# Sheet1.net
KiCad netlist of a schematic drawn in Altium Designer
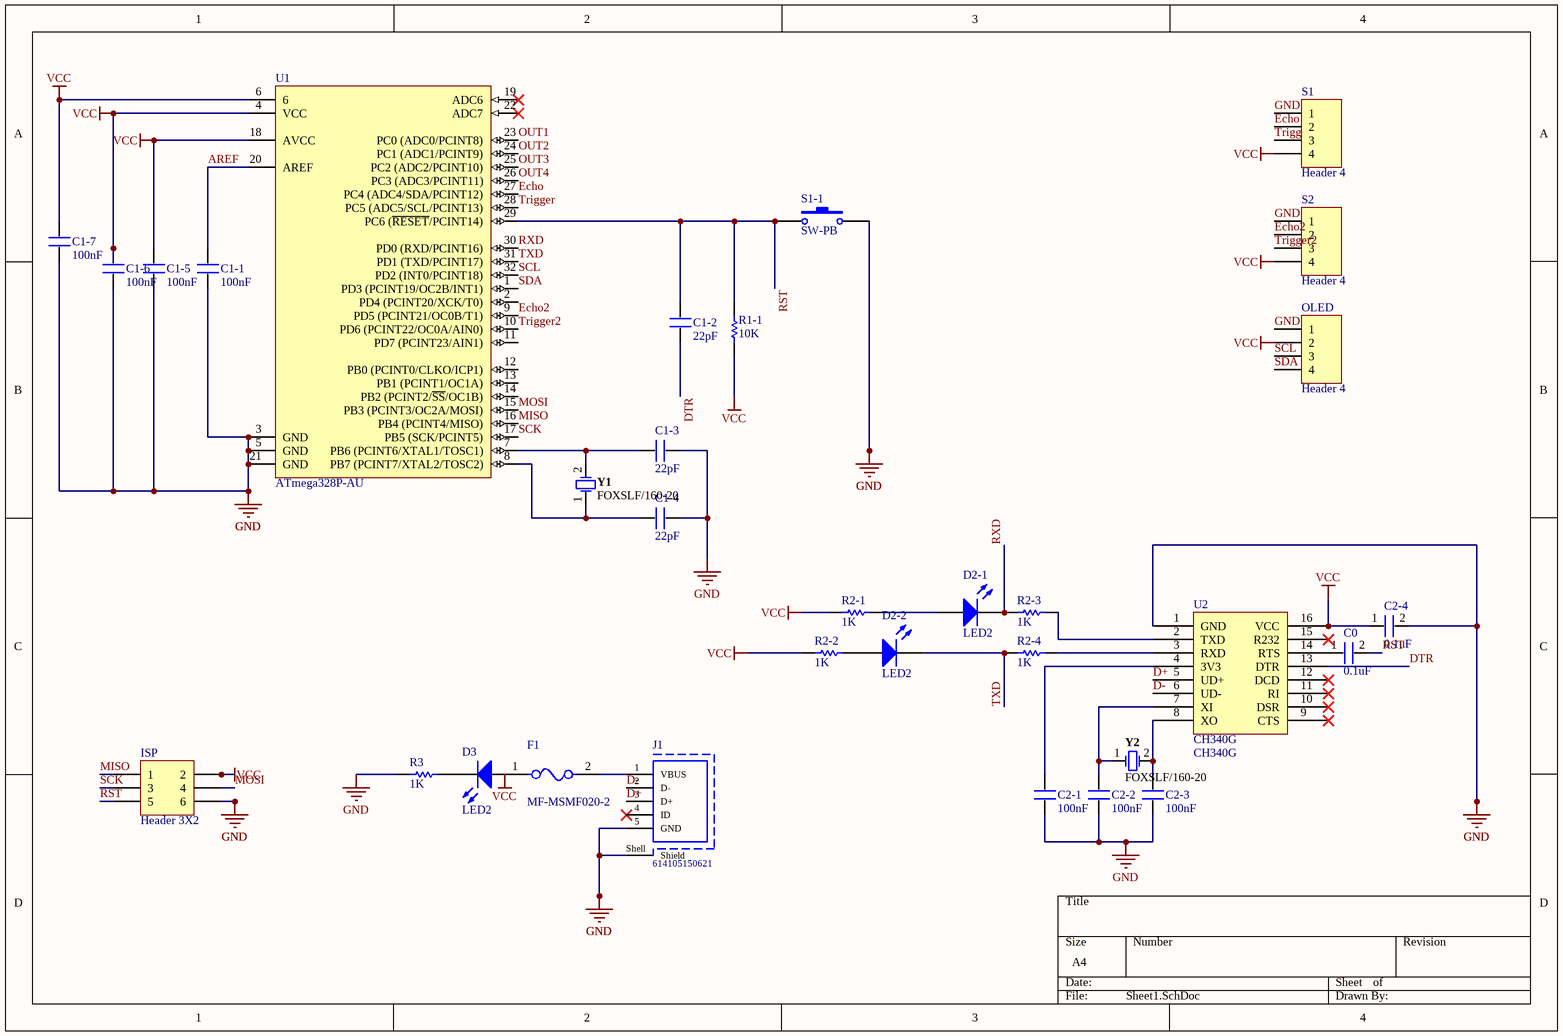
[diagram p0: Sheet1.SchDoc]

(export (version "E")
  (design (tool "Eeschema 10.0.6"))
  (components
    (comp (ref "C0")
      (value "0.1uF")
      (footprint "0805")
      (description "Capacitor")
      (fields (field (name "Comment") "CAP"))
      (libsource (lib "") (part "CAP_1"))
    )
    (comp (ref "C1-1")
      (value "100nF")
      (footprint "0805")
      (description "Capacitor")
      (fields (field (name "Comment") "CAP"))
      (libsource (lib "lib") (part "CAP"))
    )
    (comp (ref "C1-2")
      (value "22pF")
      (footprint "0805")
      (description "Capacitor")
      (fields (field (name "Comment") "CAP"))
      (libsource (lib "lib") (part "CAP"))
    )
    (comp (ref "C1-3")
      (value "22pF")
      (footprint "0805")
      (description "Capacitor")
      (fields (field (name "Comment") "CAP"))
      (libsource (lib "lib") (part "CAP"))
    )
    (comp (ref "C1-4")
      (value "22pF")
      (footprint "0805")
      (description "Capacitor")
      (fields (field (name "Comment") "CAP"))
      (libsource (lib "lib") (part "CAP"))
    )
    (comp (ref "C1-5")
      (value "100nF")
      (footprint "0805")
      (description "Capacitor")
      (fields (field (name "Comment") "CAP"))
      (libsource (lib "lib") (part "CAP"))
    )
    (comp (ref "C1-6")
      (value "100nF")
      (footprint "0805")
      (description "Capacitor")
      (fields (field (name "Comment") "CAP"))
      (libsource (lib "lib") (part "CAP"))
    )
    (comp (ref "C1-7")
      (value "100nF")
      (footprint "0805")
      (description "Capacitor")
      (fields (field (name "Comment") "CAP"))
      (libsource (lib "lib") (part "CAP"))
    )
    (comp (ref "C2-1")
      (value "100nF")
      (footprint "0805")
      (description "Capacitor")
      (fields (field (name "Comment") "CAP"))
      (libsource (lib "lib") (part "CAP"))
    )
    (comp (ref "C2-2")
      (value "100nF")
      (footprint "0805")
      (description "Capacitor")
      (fields (field (name "Comment") "CAP"))
      (libsource (lib "lib") (part "CAP"))
    )
    (comp (ref "C2-3")
      (value "100nF")
      (footprint "0805")
      (description "Capacitor")
      (fields (field (name "Comment") "CAP"))
      (libsource (lib "lib") (part "CAP"))
    )
    (comp (ref "C2-4")
      (value "0.1uF")
      (footprint "0805")
      (description "Capacitor")
      (fields (field (name "Comment") "CAP"))
      (libsource (lib "") (part "CAP_1"))
    )
    (comp (ref "D2-1")
      (value "LED2")
      (footprint "3.2X1.6X1.1")
      (description "Typical RED, GREEN, YELLOW, AMBER GaAs LED")
      (fields (field (name "PUBLISHER") "Altium Limited"))
      (libsource (lib "lib") (part "LED2"))
    )
    (comp (ref "D2-2")
      (value "LED2")
      (footprint "3.2X1.6X1.1")
      (description "Typical RED, GREEN, YELLOW, AMBER GaAs LED")
      (fields (field (name "PUBLISHER") "Altium Limited"))
      (libsource (lib "lib") (part "LED2"))
    )
    (comp (ref "D3")
      (value "LED2")
      (footprint "3.2X1.6X1.1")
      (description "Typical RED, GREEN, YELLOW, AMBER GaAs LED")
      (fields (field (name "PUBLISHER") "Altium Limited"))
      (libsource (lib "lib") (part "LED2"))
    )
    (comp (ref "F1")
      (value "MF-MSMF020-2")
      (footprint "FP-MF-MSMF020-2-MFG")
      (description "PTC RESET FUSE 30V 200MA 1812")
      (fields
        (field (name "MANUFACTURER") "Bourns")
        (field (name "OCTOPART") "https://octopart.com/mf-msmf020-2-bourns-19289")
      )
      (libsource (lib "lib") (part "CMP-07400-000027-1"))
    )
    (comp (ref "ISP")
      (value "Header 3X2")
      (footprint "HDR2X3")
      (description "Header, 3-Pin, Dual row")
      (fields (field (name "PUBLISHER") "Altium Limited"))
      (libsource (lib "Miscellaneous Connectors") (part "Header 3X2"))
    )
    (comp (ref "J1")
      (value "614105150621")
      (footprint "629105150921")
      (description "Micro USB 2.0 Type AB Receptacle WR-COM, Vertical, THT")
      (fields (field (name "MANUFACTURER") "Wurth Elektronik") (field (name "PUBLISHER") "WurthElektronik"))
      (libsource (lib "lib") (part "CMP-1502-03251-1"))
    )
    (comp (ref "OLED")
      (value "Header 4")
      (footprint "HDR1X4")
      (description "Header, 4-Pin")
      (fields (field (name "PUBLISHER") "Altium Limited"))
      (libsource (lib "Miscellaneous Connectors") (part "Header 4"))
    )
    (comp (ref "R1-1")
      (value "RES")
      (footprint "0805")
      (description "Resistor")
      (fields (field (name "VAULE") "10K"))
      (libsource (lib "lib") (part "RES"))
    )
    (comp (ref "R2-1")
      (value "RES")
      (footprint "0805")
      (description "Resistor")
      (fields (field (name "VAULE") "1K"))
      (libsource (lib "lib") (part "RES"))
    )
    (comp (ref "R2-2")
      (value "RES")
      (footprint "0805")
      (description "Resistor")
      (fields (field (name "VAULE") "1K"))
      (libsource (lib "lib") (part "RES"))
    )
    (comp (ref "R2-3")
      (value "RES")
      (footprint "0805")
      (description "Resistor")
      (fields (field (name "VAULE") "1K"))
      (libsource (lib "lib") (part "RES"))
    )
    (comp (ref "R2-4")
      (value "RES")
      (footprint "0805")
      (description "Resistor")
      (fields (field (name "VAULE") "1K"))
      (libsource (lib "lib") (part "RES"))
    )
    (comp (ref "R3")
      (value "RES")
      (footprint "0805")
      (description "Resistor")
      (fields (field (name "VAULE") "1K"))
      (libsource (lib "lib") (part "RES"))
    )
    (comp (ref "S1")
      (value "Header 4")
      (footprint "HDR1X4")
      (description "Header, 4-Pin")
      (fields (field (name "PUBLISHER") "Altium Limited"))
      (libsource (lib "Miscellaneous Connectors") (part "Header 4"))
    )
    (comp (ref "S1-1")
      (value "SW-PB")
      (footprint "SPST-2")
      (description "Switch")
      (fields (field (name "PUBLISHER") "Altium Limited"))
      (libsource (lib "lib") (part "SW-PB"))
    )
    (comp (ref "S2")
      (value "Header 4")
      (footprint "HDR1X4")
      (description "Header, 4-Pin")
      (fields (field (name "PUBLISHER") "Altium Limited"))
      (libsource (lib "Miscellaneous Connectors") (part "Header 4"))
    )
    (comp (ref "U1")
      (value "ATmega328P-AU")
      (footprint "32A_L - duplicate")
      (libsource (lib "lib") (part "CMP-0095-00269-2"))
    )
    (comp (ref "U2")
      (value "CH340G")
      (footprint "SOIC127P600X170-16N")
      (libsource (lib "lib") (part "CH340G"))
    )
    (comp (ref "Y1")
      (value "FOXSLF/160-20")
      (footprint "FOX-FOXSLF160-20")
      (description "Resistance Weld Thru-Hole Crystal, 16 MHz, -20 to 70 degC, 2-Pin THD, RoHS, Bulk")
      (fields (field (name "TOLERANCE") "1%"))
      (libsource (lib "lib") (part "CMP-1749-00003-1"))
    )
    (comp (ref "Y2")
      (value "FOXSLF/160-20")
      (footprint "FOX-FOXSLF160-20")
      (description "Resistance Weld Thru-Hole Crystal, 16 MHz, -20 to 70 degC, 2-Pin THD, RoHS, Bulk")
      (fields (field (name "TOLERANCE") "1%"))
      (libsource (lib "lib") (part "CMP-1749-00003-1"))
    )
  )
  (nets
    (net (code "1") (name "/AREF") (class "Default")
      (node (ref "C1-1") (pin "2") (pintype "passive"))
      (node (ref "U1") (pin "20") (pinfunction "AREF_20") (pintype "passive"))
    )
    (net (code "2") (name "/D+") (class "Default")
      (node (ref "J1") (pin "3") (pinfunction "D+_3") (pintype "passive"))
      (node (ref "U2") (pin "5") (pinfunction "UD+_5") (pintype "passive"))
    )
    (net (code "3") (name "/D-") (class "Default")
      (node (ref "J1") (pin "2") (pinfunction "D-_2") (pintype "passive"))
      (node (ref "U2") (pin "6") (pinfunction "UD-_6") (pintype "passive"))
    )
    (net (code "4") (name "/DTR") (class "Default")
      (node (ref "C1-2") (pin "1") (pintype "passive"))
      (node (ref "U2") (pin "13") (pinfunction "DTR_13") (pintype "passive"))
    )
    (net (code "5") (name "/Echo") (class "Default")
      (node (ref "S1") (pin "2") (pinfunction "2_2") (pintype "passive"))
      (node (ref "U1") (pin "27") (pinfunction "PC4_(ADC4/SDA/PCINT12)_27") (pintype "bidirectional"))
    )
    (net (code "6") (name "/Echo2") (class "Default")
      (node (ref "S2") (pin "2") (pinfunction "2_2") (pintype "passive"))
      (node (ref "U1") (pin "9") (pinfunction "PD5_(PCINT21/OC0B/T1)_9") (pintype "bidirectional"))
    )
    (net (code "7") (name "/MISO") (class "Default")
      (node (ref "ISP") (pin "1") (pinfunction "1_1") (pintype "passive"))
      (node (ref "U1") (pin "16") (pinfunction "PB4_(PCINT4/MISO)_16") (pintype "bidirectional"))
    )
    (net (code "8") (name "/MOSI") (class "Default")
      (node (ref "ISP") (pin "4") (pinfunction "4_4") (pintype "passive"))
      (node (ref "U1") (pin "15") (pinfunction "PB3_(PCINT3/OC2A/MOSI)_15") (pintype "bidirectional"))
    )
    (net (code "9") (name "/OUT1") (class "Default")
      (node (ref "U1") (pin "23") (pinfunction "PC0_(ADC0/PCINT8)_23") (pintype "bidirectional"))
    )
    (net (code "10") (name "/OUT2") (class "Default")
      (node (ref "U1") (pin "24") (pinfunction "PC1_(ADC1/PCINT9)_24") (pintype "bidirectional"))
    )
    (net (code "11") (name "/OUT3") (class "Default")
      (node (ref "U1") (pin "25") (pinfunction "PC2_(ADC2/PCINT10)_25") (pintype "bidirectional"))
    )
    (net (code "12") (name "/OUT4") (class "Default")
      (node (ref "U1") (pin "26") (pinfunction "PC3_(ADC3/PCINT11)_26") (pintype "bidirectional"))
    )
    (net (code "13") (name "/RST") (class "Default")
      (node (ref "C0") (pin "2") (pinfunction "2_2") (pintype "passive"))
      (node (ref "C1-2") (pin "2") (pintype "passive"))
      (node (ref "ISP") (pin "5") (pinfunction "5_5") (pintype "passive"))
      (node (ref "R1-1") (pin "1") (pinfunction "1_1") (pintype "passive"))
      (node (ref "S1-1") (pin "1") (pinfunction "1_1") (pintype "passive"))
      (node (ref "U1") (pin "29") (pinfunction "PC6_(~{RESET}/PCINT14)_29") (pintype "bidirectional"))
    )
    (net (code "14") (name "/RXD") (class "Default")
      (node (ref "D2-1") (pin "2") (pinfunction "K_2") (pintype "passive"))
      (node (ref "R2-3") (pin "1") (pinfunction "1_1") (pintype "passive"))
      (node (ref "U1") (pin "30") (pinfunction "PD0_(RXD/PCINT16)_30") (pintype "bidirectional"))
    )
    (net (code "15") (name "/SCK") (class "Default")
      (node (ref "ISP") (pin "3") (pinfunction "3_3") (pintype "passive"))
      (node (ref "U1") (pin "17") (pinfunction "PB5_(SCK/PCINT5)_17") (pintype "bidirectional"))
    )
    (net (code "16") (name "/SCL") (class "Default")
      (node (ref "OLED") (pin "3") (pinfunction "3_3") (pintype "passive"))
      (node (ref "U1") (pin "32") (pinfunction "PD2_(INT0/PCINT18)_32") (pintype "bidirectional"))
    )
    (net (code "17") (name "/SDA") (class "Default")
      (node (ref "OLED") (pin "4") (pinfunction "4_4") (pintype "passive"))
      (node (ref "U1") (pin "1") (pinfunction "PD3_(PCINT19/OC2B/INT1)_1") (pintype "bidirectional"))
    )
    (net (code "18") (name "/TXD") (class "Default")
      (node (ref "D2-2") (pin "2") (pinfunction "K_2") (pintype "passive"))
      (node (ref "R2-4") (pin "1") (pinfunction "1_1") (pintype "passive"))
      (node (ref "U1") (pin "31") (pinfunction "PD1_(TXD/PCINT17)_31") (pintype "bidirectional"))
    )
    (net (code "19") (name "/Trigger") (class "Default")
      (node (ref "S1") (pin "3") (pinfunction "3_3") (pintype "passive"))
      (node (ref "U1") (pin "28") (pinfunction "PC5_(ADC5/SCL/PCINT13)_28") (pintype "bidirectional"))
    )
    (net (code "20") (name "/Trigger2") (class "Default")
      (node (ref "S2") (pin "3") (pinfunction "3_3") (pintype "passive"))
      (node (ref "U1") (pin "10") (pinfunction "PD6_(PCINT22/OC0A/AIN0)_10") (pintype "bidirectional"))
    )
    (net (code "21") (name "GND") (class "Default")
      (node (ref "C1-1") (pin "1") (pintype "passive"))
      (node (ref "C1-3") (pin "2") (pintype "passive"))
      (node (ref "C1-4") (pin "2") (pintype "passive"))
      (node (ref "C1-5") (pin "1") (pintype "passive"))
      (node (ref "C1-6") (pin "1") (pintype "passive"))
      (node (ref "C1-7") (pin "1") (pintype "passive"))
      (node (ref "C2-1") (pin "1") (pintype "passive"))
      (node (ref "C2-2") (pin "1") (pintype "passive"))
      (node (ref "C2-3") (pin "1") (pintype "passive"))
      (node (ref "C2-4") (pin "2") (pinfunction "2_2") (pintype "passive"))
      (node (ref "ISP") (pin "6") (pinfunction "6_6") (pintype "passive"))
      (node (ref "J1") (pin "5") (pinfunction "GND_5") (pintype "passive"))
      (node (ref "J1") (pin "Shell") (pinfunction "Shield_Shell") (pintype "passive"))
      (node (ref "OLED") (pin "1") (pinfunction "1_1") (pintype "passive"))
      (node (ref "R3") (pin "1") (pinfunction "1_1") (pintype "passive"))
      (node (ref "S1") (pin "1") (pinfunction "1_1") (pintype "passive"))
      (node (ref "S1-1") (pin "2") (pinfunction "2_2") (pintype "passive"))
      (node (ref "S2") (pin "1") (pinfunction "1_1") (pintype "passive"))
      (node (ref "U1") (pin "21") (pinfunction "GND_21") (pintype "power_in"))
      (node (ref "U1") (pin "3") (pinfunction "GND_3") (pintype "power_in"))
      (node (ref "U1") (pin "5") (pinfunction "GND_5") (pintype "power_in"))
      (node (ref "U2") (pin "1") (pinfunction "GND_1") (pintype "passive"))
    )
    (net (code "22") (name "Net-(D2-1-A)") (class "Default")
      (node (ref "D2-1") (pin "1") (pinfunction "A_1") (pintype "passive"))
      (node (ref "R2-1") (pin "2") (pinfunction "2_2") (pintype "passive"))
    )
    (net (code "23") (name "Net-(D2-2-A)") (class "Default")
      (node (ref "D2-2") (pin "1") (pinfunction "A_1") (pintype "passive"))
      (node (ref "R2-2") (pin "2") (pinfunction "2_2") (pintype "passive"))
    )
    (net (code "24") (name "Net-(D3-K)") (class "Default")
      (node (ref "D3") (pin "2") (pinfunction "K_2") (pintype "passive"))
      (node (ref "R3") (pin "2") (pinfunction "2_2") (pintype "passive"))
    )
    (net (code "25") (name "Net-(J1-VBUS)") (class "Default")
      (node (ref "F1") (pin "2") (pinfunction "2_2") (pintype "passive"))
      (node (ref "J1") (pin "1") (pinfunction "VBUS_1") (pintype "passive"))
    )
    (net (code "26") (name "Net-(U1-PB6_(PCINT6{slash}XTAL1{slash}TOSC1))") (class "Default")
      (node (ref "C1-3") (pin "1") (pintype "passive"))
      (node (ref "U1") (pin "7") (pinfunction "PB6_(PCINT6/XTAL1/TOSC1)_7") (pintype "bidirectional"))
      (node (ref "Y1") (pin "2") (pinfunction "2_2") (pintype "passive"))
    )
    (net (code "27") (name "Net-(U1-PB7_(PCINT7{slash}XTAL2{slash}TOSC2))") (class "Default")
      (node (ref "C1-4") (pin "1") (pintype "passive"))
      (node (ref "U1") (pin "8") (pinfunction "PB7_(PCINT7/XTAL2/TOSC2)_8") (pintype "bidirectional"))
      (node (ref "Y1") (pin "1") (pinfunction "1_1") (pintype "passive"))
    )
    (net (code "28") (name "Net-(U2-3V3)") (class "Default")
      (node (ref "C2-1") (pin "2") (pintype "passive"))
      (node (ref "U2") (pin "4") (pinfunction "3V3_4") (pintype "passive"))
    )
    (net (code "29") (name "Net-(U2-RTS)") (class "Default")
      (node (ref "C0") (pin "1") (pinfunction "1_1") (pintype "passive"))
      (node (ref "U2") (pin "14") (pinfunction "RTS_14") (pintype "passive"))
    )
    (net (code "30") (name "Net-(U2-RXD)") (class "Default")
      (node (ref "R2-4") (pin "2") (pinfunction "2_2") (pintype "passive"))
      (node (ref "U2") (pin "3") (pinfunction "RXD_3") (pintype "passive"))
    )
    (net (code "31") (name "Net-(U2-TXD)") (class "Default")
      (node (ref "R2-3") (pin "2") (pinfunction "2_2") (pintype "passive"))
      (node (ref "U2") (pin "2") (pinfunction "TXD_2") (pintype "passive"))
    )
    (net (code "32") (name "Net-(U2-XI)") (class "Default")
      (node (ref "C2-2") (pin "2") (pintype "passive"))
      (node (ref "U2") (pin "7") (pinfunction "XI_7") (pintype "passive"))
      (node (ref "Y2") (pin "1") (pinfunction "1_1") (pintype "passive"))
    )
    (net (code "33") (name "Net-(U2-XO)") (class "Default")
      (node (ref "C2-3") (pin "2") (pintype "passive"))
      (node (ref "U2") (pin "8") (pinfunction "XO_8") (pintype "passive"))
      (node (ref "Y2") (pin "2") (pinfunction "2_2") (pintype "passive"))
    )
    (net (code "34") (name "VCC") (class "Default")
      (node (ref "C1-5") (pin "2") (pintype "passive"))
      (node (ref "C1-6") (pin "2") (pintype "passive"))
      (node (ref "C1-7") (pin "2") (pintype "passive"))
      (node (ref "C2-4") (pin "1") (pinfunction "1_1") (pintype "passive"))
      (node (ref "F1") (pin "1") (pinfunction "1_1") (pintype "passive"))
      (node (ref "ISP") (pin "2") (pinfunction "2_2") (pintype "passive"))
      (node (ref "OLED") (pin "2") (pinfunction "2_2") (pintype "passive"))
      (node (ref "R1-1") (pin "2") (pinfunction "2_2") (pintype "passive"))
      (node (ref "R2-1") (pin "1") (pinfunction "1_1") (pintype "passive"))
      (node (ref "R2-2") (pin "1") (pinfunction "1_1") (pintype "passive"))
      (node (ref "S1") (pin "4") (pinfunction "4_4") (pintype "passive"))
      (node (ref "S2") (pin "4") (pinfunction "4_4") (pintype "passive"))
      (node (ref "U1") (pin "18") (pinfunction "AVCC_18") (pintype "power_in"))
      (node (ref "U1") (pin "4") (pinfunction "VCC_4") (pintype "power_in"))
      (node (ref "U1") (pin "6") (pinfunction "6_6") (pintype "power_in"))
      (node (ref "U2") (pin "16") (pinfunction "VCC_16") (pintype "passive"))
    )
    (net (code "35") (name "unconnected-(D3-A-Pad1)") (class "Default")
      (node (ref "D3") (pin "1") (pinfunction "A_1") (pintype "passive"))
    )
    (net (code "36") (name "unconnected-(J1-ID-Pad4)") (class "Default")
      (node (ref "J1") (pin "4") (pinfunction "ID_4") (pintype "passive+no_connect"))
    )
    (net (code "37") (name "unconnected-(U1-ADC6-Pad19)") (class "Default")
      (node (ref "U1") (pin "19") (pinfunction "ADC6_19") (pintype "input+no_connect"))
    )
    (net (code "38") (name "unconnected-(U1-ADC7-Pad22)") (class "Default")
      (node (ref "U1") (pin "22") (pinfunction "ADC7_22") (pintype "input+no_connect"))
    )
    (net (code "39") (name "unconnected-(U1-PB0_(PCINT0{slash}CLKO{slash}ICP1)-Pad12)") (class "Default")
      (node (ref "U1") (pin "12") (pinfunction "PB0_(PCINT0/CLKO/ICP1)_12") (pintype "bidirectional"))
    )
    (net (code "40") (name "unconnected-(U1-PB1_(PCINT1{slash}OC1A)-Pad13)") (class "Default")
      (node (ref "U1") (pin "13") (pinfunction "PB1_(PCINT1/OC1A)_13") (pintype "bidirectional"))
    )
    (net (code "41") (name "unconnected-(U1-PB2_(PCINT2{slash}~{SS}{slash}OC1B)-Pad14)") (class "Default")
      (node (ref "U1") (pin "14") (pinfunction "PB2_(PCINT2/~{SS}/OC1B)_14") (pintype "bidirectional"))
    )
    (net (code "42") (name "unconnected-(U1-PD4_(PCINT20{slash}XCK{slash}T0)-Pad2)") (class "Default")
      (node (ref "U1") (pin "2") (pinfunction "PD4_(PCINT20/XCK/T0)_2") (pintype "bidirectional"))
    )
    (net (code "43") (name "unconnected-(U1-PD7_(PCINT23{slash}AIN1)-Pad11)") (class "Default")
      (node (ref "U1") (pin "11") (pinfunction "PD7_(PCINT23/AIN1)_11") (pintype "bidirectional"))
    )
    (net (code "44") (name "unconnected-(U2-CTS-Pad9)") (class "Default")
      (node (ref "U2") (pin "9") (pinfunction "CTS_9") (pintype "passive+no_connect"))
    )
    (net (code "45") (name "unconnected-(U2-DCD-Pad12)") (class "Default")
      (node (ref "U2") (pin "12") (pinfunction "DCD_12") (pintype "passive+no_connect"))
    )
    (net (code "46") (name "unconnected-(U2-DSR-Pad10)") (class "Default")
      (node (ref "U2") (pin "10") (pinfunction "DSR_10") (pintype "passive+no_connect"))
    )
    (net (code "47") (name "unconnected-(U2-R232-Pad15)") (class "Default")
      (node (ref "U2") (pin "15") (pinfunction "R232_15") (pintype "passive+no_connect"))
    )
    (net (code "48") (name "unconnected-(U2-RI-Pad11)") (class "Default")
      (node (ref "U2") (pin "11") (pinfunction "RI_11") (pintype "passive+no_connect"))
    )
  )
)
